# Logic.net
KiCad netlist of a schematic drawn in Altium Designer
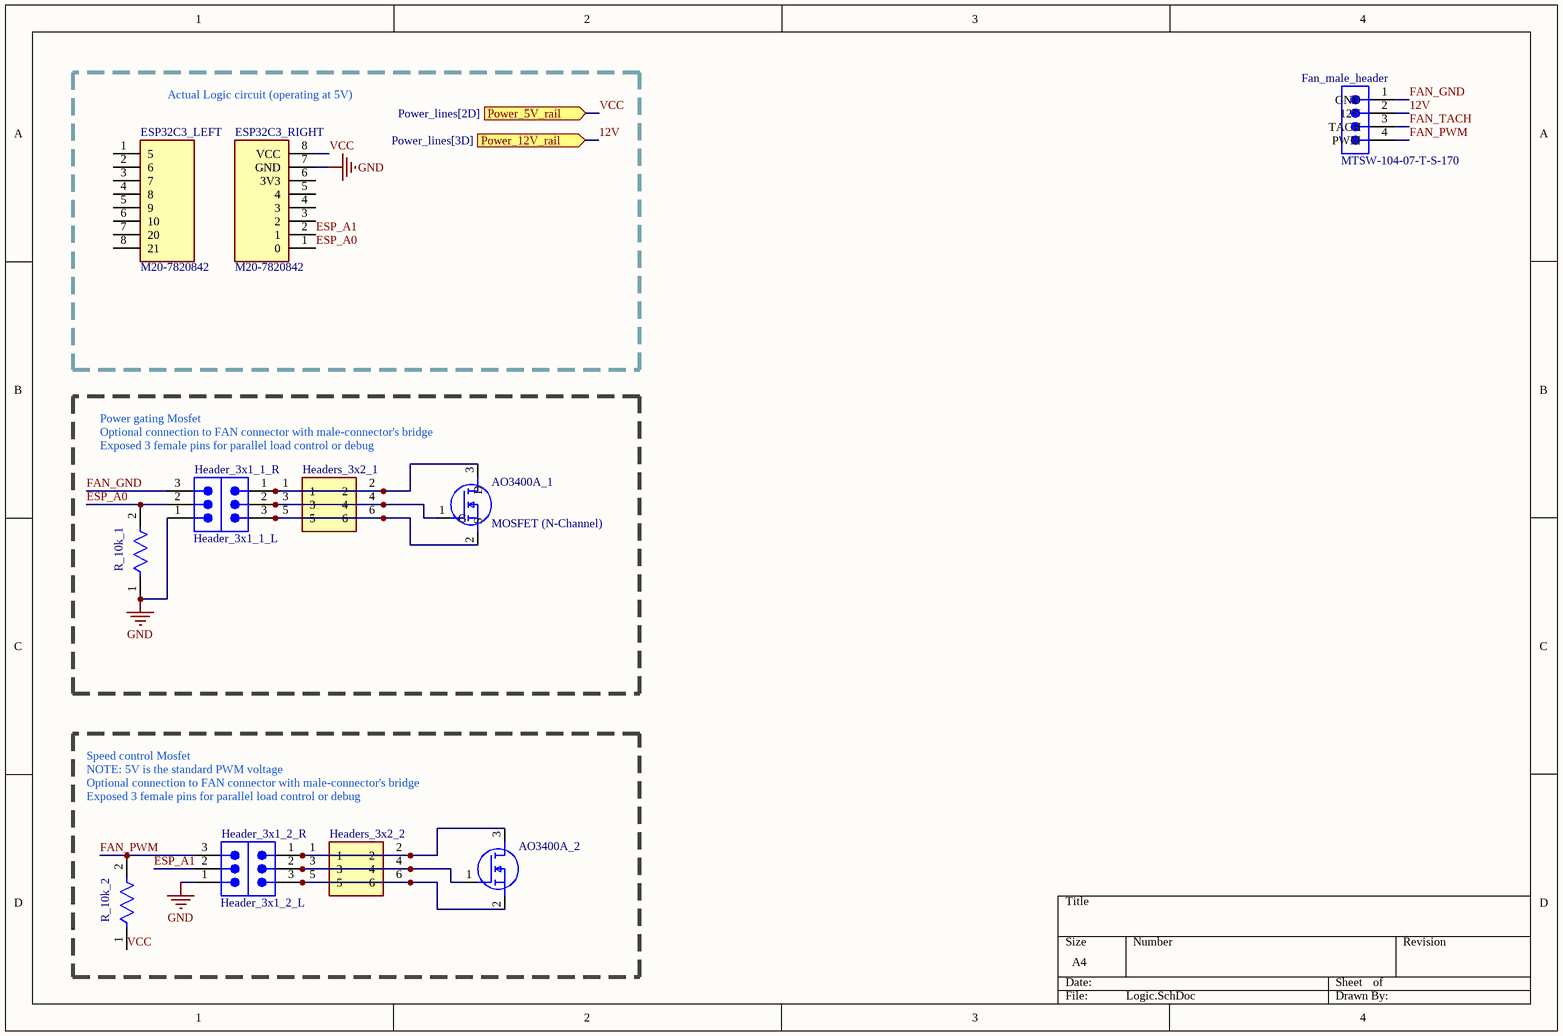
[diagram p0: Logic.SchDoc]

(export (version "E")
  (design (tool "Eeschema 10.0.6"))
  (components
    (comp (ref "AO3400A_1")
      (value "MOSFET (N-Channel)")
      (footprint "SamacSys:SOT95P280X125-3N")
      (fields (field (name "MANUFACTURER_PART_NUMBER") "AO3400A"))
      (libsource (lib "") (part "AO3400A_1"))
    )
    (comp (ref "AO3400A_2")
      (value "MOSFET (N-Channel)")
      (footprint "SamacSys:SOT95P280X125-3N")
      (fields (field (name "MANUFACTURER_PART_NUMBER") "AO3400A"))
      (libsource (lib "*") (part "AO3400A"))
    )
    (comp (ref "ESP32C3_LEFT")
      (value "M20-7820842")
      (footprint "SamacSys:RHDR8W80P0X254_1X8_2032X254X850P")
      (description "Connector")
      (fields (field (name "MOUSER PART NUMBER") "855-M20-7820842"))
      (libsource (lib "") (part "M20-7820842_1"))
    )
    (comp (ref "ESP32C3_RIGHT")
      (value "M20-7820842")
      (footprint "SamacSys:RHDR8W80P0X254_1X8_2032X254X850P")
      (description "Connector")
      (fields (field (name "MOUSER PART NUMBER") "855-M20-7820842"))
      (libsource (lib "*") (part "M20-7820842"))
    )
    (comp (ref "Fan_male_header")
      (value "MTSW-104-07-T-S-170")
      (footprint "SMTC-MTSW-104-07-X-S-170")
      (fields (field (name "MANUFACTURER") "Samtec"))
      (libsource (lib "Altium Content Vault") (part "SMTC-MTSW-104-07-X-S-170"))
    )
    (comp (ref "Headers_3x2_1")
      (value "Female header 3x2")
      (footprint "SamacSys:RHDR6W50P200X200_2X3_650X400X430P")
      (description "Connector")
      (fields
        (field (name "MANUFACTURER_PART_NUMBER") "M22-7140342")
        (field (name "MOUSER PART NUMBER") "855-M22-7140342")
      )
      (libsource (lib "*") (part "M22-7140342"))
    )
    (comp (ref "Headers_3x2_2")
      (value "Female header 3x2")
      (footprint "SamacSys:RHDR6W50P200X200_2X3_650X400X430P")
      (description "Connector")
      (fields
        (field (name "MANUFACTURER_PART_NUMBER") "M22-7140342")
        (field (name "MOUSER PART NUMBER") "855-M22-7140342")
      )
      (libsource (lib "*") (part "M22-7140342"))
    )
    (comp (ref "Header_3x1_1_L")
      (value "TSW-103-07-T-S")
      (footprint "SMTC-TSW-103-07-X-S")
      (description "0.025\" SQ Post Header, Through-hole, Vertical, -55 to 105 degC, 2.54 mm Pitch, 3-Pin, Male, RoHS")
      (fields (field (name "MANUFACTURER") "Samtec"))
      (libsource (lib "Altium Content Vault") (part "SMTC-TSW-103-X-X-S-X"))
    )
    (comp (ref "Header_3x1_1_R")
      (value "TSW-103-07-T-S")
      (footprint "SMTC-TSW-103-07-X-S")
      (description "0.025\" SQ Post Header, Through-hole, Vertical, -55 to 105 degC, 2.54 mm Pitch, 3-Pin, Male, RoHS")
      (fields (field (name "MANUFACTURER") "Samtec"))
      (libsource (lib "Altium Content Vault") (part "SMTC-TSW-103-X-X-S-X"))
    )
    (comp (ref "Header_3x1_2_L")
      (value "TSW-103-07-T-S")
      (footprint "SMTC-TSW-103-07-X-S")
      (description "0.025\" SQ Post Header, Through-hole, Vertical, -55 to 105 degC, 2.54 mm Pitch, 3-Pin, Male, RoHS")
      (fields (field (name "MANUFACTURER") "Samtec"))
      (libsource (lib "Altium Content Vault") (part "SMTC-TSW-103-X-X-S-X"))
    )
    (comp (ref "Header_3x1_2_R")
      (value "TSW-103-07-T-S")
      (footprint "SMTC-TSW-103-07-X-S")
      (description "0.025\" SQ Post Header, Through-hole, Vertical, -55 to 105 degC, 2.54 mm Pitch, 3-Pin, Male, RoHS")
      (fields (field (name "MANUFACTURER") "Samtec"))
      (libsource (lib "Altium Content Vault") (part "SMTC-TSW-103-X-X-S-X"))
    )
    (comp (ref "R_10k_1")
      (value "CRGCQ1206F10K")
      (footprint "FP-CRGCQ1206-IPC_C")
      (description "CRGCQ1206 10KΩ 0.25W 1% ±100ppm/°C 200V")
      (fields (field (name "MANUFACTURER") "TE Connectivity") (field (name "TOLERANCE") "0.01"))
      (libsource (lib "Altium Content Vault") (part "1029c3af85768c4190bb7ad29bc67b5"))
    )
    (comp (ref "R_10k_2")
      (value "CRGCQ1206F10K")
      (footprint "FP-CRGCQ1206-IPC_C")
      (description "CRGCQ1206 10KΩ 0.25W 1% ±100ppm/°C 200V")
      (fields (field (name "MANUFACTURER") "TE Connectivity") (field (name "TOLERANCE") "0.01"))
      (libsource (lib "Altium Content Vault") (part "1029c3af85768c4190bb7ad29bc67b5"))
    )
  )
  (nets
    (net (code "1") (name "/12V") (class "Default")
      (node (ref "Fan_male_header") (pin "2") (pinfunction "12V_2") (pintype "passive"))
    )
    (net (code "2") (name "/ESP_A0") (class "Default")
      (node (ref "ESP32C3_RIGHT") (pin "1") (pinfunction "0_1") (pintype "passive"))
      (node (ref "Header_3x1_1_L") (pin "2") (pinfunction "2_2") (pintype "passive"))
      (node (ref "R_10k_1") (pin "2") (pinfunction "2_2") (pintype "passive"))
    )
    (net (code "3") (name "/ESP_A1") (class "Default")
      (node (ref "ESP32C3_RIGHT") (pin "2") (pinfunction "1_2") (pintype "passive"))
      (node (ref "Header_3x1_2_L") (pin "2") (pinfunction "2_2") (pintype "passive"))
    )
    (net (code "4") (name "/FAN_GND") (class "Default")
      (node (ref "Fan_male_header") (pin "1") (pinfunction "GND_1") (pintype "passive"))
      (node (ref "Header_3x1_1_L") (pin "3") (pinfunction "3_3") (pintype "passive"))
    )
    (net (code "5") (name "/FAN_PWM") (class "Default")
      (node (ref "Fan_male_header") (pin "4") (pinfunction "PWM_4") (pintype "passive"))
      (node (ref "Header_3x1_2_L") (pin "3") (pinfunction "3_3") (pintype "passive"))
      (node (ref "R_10k_2") (pin "2") (pinfunction "2_2") (pintype "passive"))
    )
    (net (code "6") (name "/FAN_TACH") (class "Default")
      (node (ref "Fan_male_header") (pin "3") (pinfunction "TACH_3") (pintype "passive"))
    )
    (net (code "7") (name "/VCC") (class "Default")
      (node (ref "ESP32C3_RIGHT") (pin "8") (pinfunction "VCC_8") (pintype "passive"))
      (node (ref "R_10k_2") (pin "1") (pinfunction "1_1") (pintype "passive"))
    )
    (net (code "8") (name "GND") (class "Default")
      (node (ref "ESP32C3_RIGHT") (pin "7") (pinfunction "GND_7") (pintype "passive"))
      (node (ref "Header_3x1_1_L") (pin "1") (pinfunction "1_1") (pintype "passive"))
      (node (ref "Header_3x1_2_L") (pin "1") (pinfunction "1_1") (pintype "passive"))
      (node (ref "R_10k_1") (pin "1") (pinfunction "1_1") (pintype "passive"))
    )
    (net (code "9") (name "Net-(AO3400A_1-D)") (class "Default")
      (node (ref "AO3400A_1") (pin "3") (pinfunction "D_3") (pintype "passive"))
      (node (ref "Header_3x1_1_R") (pin "1") (pinfunction "1_1") (pintype "passive"))
      (node (ref "Headers_3x2_1") (pin "1") (pinfunction "1_1") (pintype "passive"))
      (node (ref "Headers_3x2_1") (pin "2") (pinfunction "2_2") (pintype "passive"))
    )
    (net (code "10") (name "Net-(AO3400A_1-G)") (class "Default")
      (node (ref "AO3400A_1") (pin "1") (pinfunction "G_1") (pintype "passive"))
      (node (ref "Header_3x1_1_R") (pin "2") (pinfunction "2_2") (pintype "passive"))
      (node (ref "Headers_3x2_1") (pin "3") (pinfunction "3_3") (pintype "passive"))
      (node (ref "Headers_3x2_1") (pin "4") (pinfunction "4_4") (pintype "passive"))
    )
    (net (code "11") (name "Net-(AO3400A_1-S)") (class "Default")
      (node (ref "AO3400A_1") (pin "2") (pinfunction "S_2") (pintype "passive"))
      (node (ref "Header_3x1_1_R") (pin "3") (pinfunction "3_3") (pintype "passive"))
      (node (ref "Headers_3x2_1") (pin "5") (pinfunction "5_5") (pintype "passive"))
      (node (ref "Headers_3x2_1") (pin "6") (pinfunction "6_6") (pintype "passive"))
    )
    (net (code "12") (name "Net-(AO3400A_2-D)") (class "Default")
      (node (ref "AO3400A_2") (pin "3") (pinfunction "D_3") (pintype "passive"))
      (node (ref "Header_3x1_2_R") (pin "1") (pinfunction "1_1") (pintype "passive"))
      (node (ref "Headers_3x2_2") (pin "1") (pinfunction "1_1") (pintype "passive"))
      (node (ref "Headers_3x2_2") (pin "2") (pinfunction "2_2") (pintype "passive"))
    )
    (net (code "13") (name "Net-(AO3400A_2-G)") (class "Default")
      (node (ref "AO3400A_2") (pin "1") (pinfunction "G_1") (pintype "passive"))
      (node (ref "Header_3x1_2_R") (pin "2") (pinfunction "2_2") (pintype "passive"))
      (node (ref "Headers_3x2_2") (pin "3") (pinfunction "3_3") (pintype "passive"))
      (node (ref "Headers_3x2_2") (pin "4") (pinfunction "4_4") (pintype "passive"))
    )
    (net (code "14") (name "Net-(AO3400A_2-S)") (class "Default")
      (node (ref "AO3400A_2") (pin "2") (pinfunction "S_2") (pintype "passive"))
      (node (ref "Header_3x1_2_R") (pin "3") (pinfunction "3_3") (pintype "passive"))
      (node (ref "Headers_3x2_2") (pin "5") (pinfunction "5_5") (pintype "passive"))
      (node (ref "Headers_3x2_2") (pin "6") (pinfunction "6_6") (pintype "passive"))
    )
    (net (code "15") (name "unconnected-(ESP32C3_LEFT-5-Pad1)") (class "Default")
      (node (ref "ESP32C3_LEFT") (pin "1") (pinfunction "5_1") (pintype "passive"))
    )
    (net (code "16") (name "unconnected-(ESP32C3_LEFT-6-Pad2)") (class "Default")
      (node (ref "ESP32C3_LEFT") (pin "2") (pinfunction "6_2") (pintype "passive"))
    )
    (net (code "17") (name "unconnected-(ESP32C3_LEFT-7-Pad3)") (class "Default")
      (node (ref "ESP32C3_LEFT") (pin "3") (pinfunction "7_3") (pintype "passive"))
    )
    (net (code "18") (name "unconnected-(ESP32C3_LEFT-8-Pad4)") (class "Default")
      (node (ref "ESP32C3_LEFT") (pin "4") (pinfunction "8_4") (pintype "passive"))
    )
    (net (code "19") (name "unconnected-(ESP32C3_LEFT-9-Pad5)") (class "Default")
      (node (ref "ESP32C3_LEFT") (pin "5") (pinfunction "9_5") (pintype "passive"))
    )
    (net (code "20") (name "unconnected-(ESP32C3_LEFT-10-Pad6)") (class "Default")
      (node (ref "ESP32C3_LEFT") (pin "6") (pinfunction "10_6") (pintype "passive"))
    )
    (net (code "21") (name "unconnected-(ESP32C3_LEFT-20-Pad7)") (class "Default")
      (node (ref "ESP32C3_LEFT") (pin "7") (pinfunction "20_7") (pintype "passive"))
    )
    (net (code "22") (name "unconnected-(ESP32C3_LEFT-21-Pad8)") (class "Default")
      (node (ref "ESP32C3_LEFT") (pin "8") (pinfunction "21_8") (pintype "passive"))
    )
    (net (code "23") (name "unconnected-(ESP32C3_RIGHT-2-Pad3)") (class "Default")
      (node (ref "ESP32C3_RIGHT") (pin "3") (pinfunction "2_3") (pintype "passive"))
    )
    (net (code "24") (name "unconnected-(ESP32C3_RIGHT-3-Pad4)") (class "Default")
      (node (ref "ESP32C3_RIGHT") (pin "4") (pinfunction "3_4") (pintype "passive"))
    )
    (net (code "25") (name "unconnected-(ESP32C3_RIGHT-3V3-Pad6)") (class "Default")
      (node (ref "ESP32C3_RIGHT") (pin "6") (pinfunction "3V3_6") (pintype "passive"))
    )
    (net (code "26") (name "unconnected-(ESP32C3_RIGHT-4-Pad5)") (class "Default")
      (node (ref "ESP32C3_RIGHT") (pin "5") (pinfunction "4_5") (pintype "passive"))
    )
  )
)
